# GearIndicator_pwr.net
KiCad netlist of a schematic drawn in EAGLE
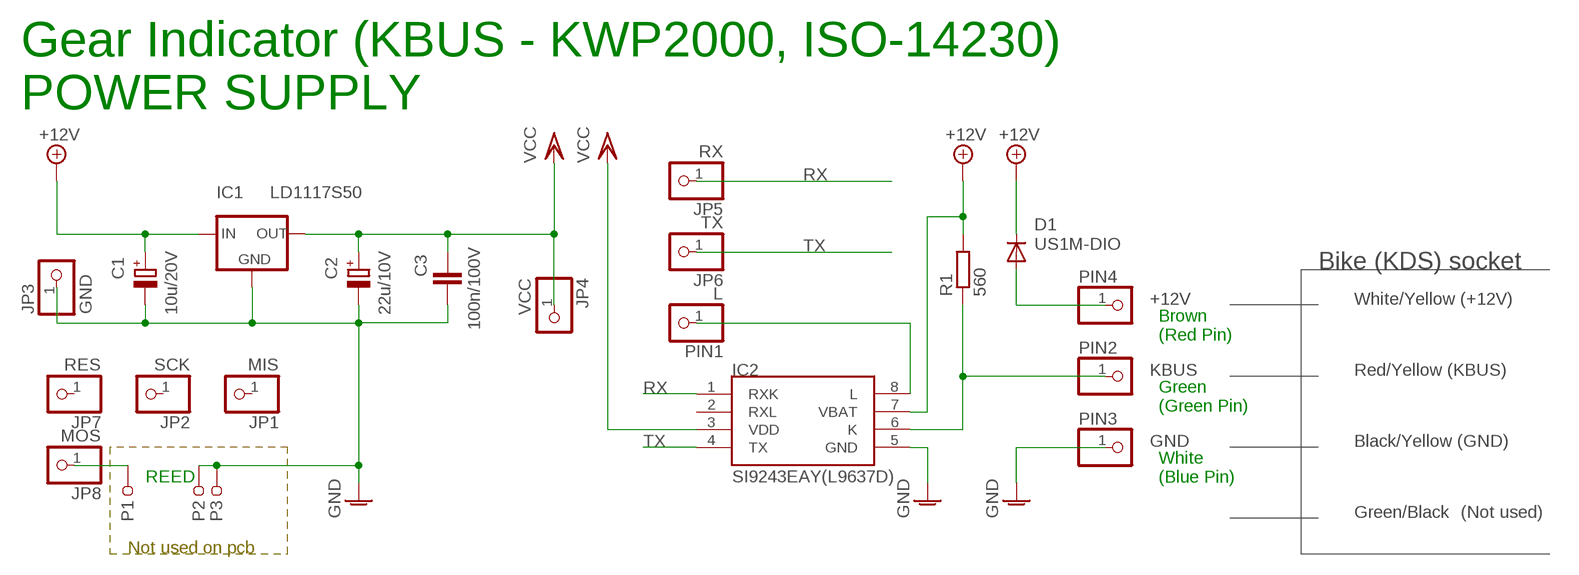
[diagram p0: schematic, sheet 1]

(export (version "E")
  (design (tool "Eeschema 10.0.6"))
  (components
    (comp (ref "C1")
      (value "10u/20V")
      (footprint "eagle-import:CT3216")
      (libsource (lib "eagle-import") (part "CPOL-EUCT3216"))
    )
    (comp (ref "C2")
      (value "22u/10V")
      (footprint "eagle-import:CT3216")
      (libsource (lib "eagle-import") (part "CPOL-EUCT3216"))
    )
    (comp (ref "C3")
      (value "100n/100V")
      (footprint "eagle-import:C1206")
      (libsource (lib "eagle-import") (part "C-EUC1206"))
    )
    (comp (ref "D1")
      (value "US1M-DIO")
      (footprint "eagle-import:DO-214AC")
      (libsource (lib "eagle-import") (part "DIODE-DO-214AC"))
    )
    (comp (ref "IC1")
      (value "LD1117S50")
      (footprint "eagle-import:SOT223")
      (libsource (lib "eagle-import") (part "AMS1117"))
    )
    (comp (ref "IC2")
      (value "SI9243EAY(L9637D)")
      (footprint "eagle-import:SO08")
      (libsource (lib "eagle-import") (part "SI9243"))
    )
    (comp (ref "JP1")
      (value "MIS")
      (footprint "eagle-import:1X01")
      (libsource (lib "eagle-import") (part "PINHD-1X1"))
    )
    (comp (ref "JP2")
      (value "SCK")
      (footprint "eagle-import:1X01")
      (libsource (lib "eagle-import") (part "PINHD-1X1"))
    )
    (comp (ref "JP3")
      (value "GND")
      (footprint "eagle-import:1X01")
      (libsource (lib "eagle-import") (part "PINHD-1X1"))
    )
    (comp (ref "JP4")
      (value "VCC")
      (footprint "eagle-import:1X01")
      (libsource (lib "eagle-import") (part "PINHD-1X1"))
    )
    (comp (ref "JP5")
      (value "RX")
      (footprint "eagle-import:1X01")
      (libsource (lib "eagle-import") (part "PINHD-1X1"))
    )
    (comp (ref "JP6")
      (value "TX")
      (footprint "eagle-import:1X01")
      (libsource (lib "eagle-import") (part "PINHD-1X1"))
    )
    (comp (ref "JP7")
      (value "RES")
      (footprint "eagle-import:1X01")
      (libsource (lib "eagle-import") (part "PINHD-1X1"))
    )
    (comp (ref "JP8")
      (value "MOS")
      (footprint "eagle-import:1X01")
      (libsource (lib "eagle-import") (part "PINHD-1X1"))
    )
    (comp (ref "P1")
      (value "SMD2")
      (footprint "eagle-import:SMD_2X1")
      (libsource (lib "eagle-import") (part "SMD2"))
    )
    (comp (ref "P2")
      (value "SMD2")
      (footprint "eagle-import:SMD_2X1")
      (libsource (lib "eagle-import") (part "SMD2"))
    )
    (comp (ref "P3")
      (value "SMD2")
      (footprint "eagle-import:SMD_2X1")
      (libsource (lib "eagle-import") (part "SMD2"))
    )
    (comp (ref "PIN1")
      (value "L")
      (footprint "eagle-import:PIN1")
      (libsource (lib "eagle-import") (part "PIN1"))
    )
    (comp (ref "PIN2")
      (value "KBUS")
      (footprint "eagle-import:PIN1")
      (libsource (lib "eagle-import") (part "PIN1"))
    )
    (comp (ref "PIN3")
      (value "GND")
      (footprint "eagle-import:PIN1")
      (libsource (lib "eagle-import") (part "PIN1"))
    )
    (comp (ref "PIN4")
      (value "+12V")
      (footprint "eagle-import:PIN1")
      (libsource (lib "eagle-import") (part "PIN1"))
    )
    (comp (ref "R1")
      (value "560")
      (footprint "eagle-import:R1206")
      (libsource (lib "eagle-import") (part "R-EU_R1206"))
    )
  )
  (nets
    (net (code "1") (name "+12V") (class "Default")
      (node (ref "C1") (pin "+") (pinfunction "+_+") (pintype "passive"))
      (node (ref "D1") (pin "C") (pinfunction "C_C") (pintype "passive"))
      (node (ref "IC1") (pin "3") (pinfunction "IN_3") (pintype "input"))
      (node (ref "IC2") (pin "7") (pinfunction "VBAT_7") (pintype "power_in"))
      (node (ref "R1") (pin "2") (pinfunction "2_2") (pintype "passive"))
    )
    (net (code "2") (name "/RX") (class "Default")
      (node (ref "IC2") (pin "1") (pinfunction "RXK_1") (pintype "bidirectional"))
      (node (ref "JP5") (pin "1") (pinfunction "1_1") (pintype "passive"))
    )
    (net (code "3") (name "/TX") (class "Default")
      (node (ref "IC2") (pin "4") (pinfunction "TX_4") (pintype "bidirectional"))
      (node (ref "JP6") (pin "1") (pinfunction "1_1") (pintype "passive"))
    )
    (net (code "4") (name "GND") (class "Default")
      (node (ref "C1") (pin "-") (pinfunction "-_-") (pintype "passive"))
      (node (ref "C2") (pin "-") (pinfunction "-_-") (pintype "passive"))
      (node (ref "C3") (pin "2") (pinfunction "2_2") (pintype "passive"))
      (node (ref "IC1") (pin "1") (pinfunction "GND_1") (pintype "input"))
      (node (ref "IC2") (pin "5") (pinfunction "GND_5") (pintype "power_in"))
      (node (ref "JP3") (pin "1") (pinfunction "1_1") (pintype "passive"))
      (node (ref "P2") (pin "P$1") (pinfunction "1_P$1") (pintype "passive"))
      (node (ref "P3") (pin "P$1") (pinfunction "1_P$1") (pintype "passive"))
      (node (ref "PIN3") (pin "1") (pinfunction "1_1") (pintype "passive"))
    )
    (net (code "5") (name "Net-(D1-PadA)") (class "Default")
      (node (ref "D1") (pin "A") (pinfunction "A_A") (pintype "passive"))
      (node (ref "PIN4") (pin "1") (pinfunction "1_1") (pintype "passive"))
    )
    (net (code "6") (name "Net-(IC2-K)") (class "Default")
      (node (ref "IC2") (pin "6") (pinfunction "K_6") (pintype "bidirectional"))
      (node (ref "PIN2") (pin "1") (pinfunction "1_1") (pintype "passive"))
      (node (ref "R1") (pin "1") (pinfunction "1_1") (pintype "passive"))
    )
    (net (code "7") (name "Net-(IC2-L)") (class "Default")
      (node (ref "IC2") (pin "8") (pinfunction "L_8") (pintype "bidirectional"))
      (node (ref "PIN1") (pin "1") (pinfunction "1_1") (pintype "passive"))
    )
    (net (code "8") (name "Net-(P1-1)") (class "Default")
      (node (ref "JP8") (pin "1") (pinfunction "1_1") (pintype "passive"))
      (node (ref "P1") (pin "P$1") (pinfunction "1_P$1") (pintype "passive"))
    )
    (net (code "9") (name "VCC") (class "Default")
      (node (ref "C2") (pin "+") (pinfunction "+_+") (pintype "passive"))
      (node (ref "C3") (pin "1") (pinfunction "1_1") (pintype "passive"))
      (node (ref "IC1") (pin "2") (pinfunction "OUT_2") (pintype "passive"))
      (node (ref "IC2") (pin "3") (pinfunction "VDD_3") (pintype "power_in"))
      (node (ref "JP4") (pin "1") (pinfunction "1_1") (pintype "passive"))
    )
    (net (code "10") (name "unconnected-(IC2-RXL-Pad2)") (class "Default")
      (node (ref "IC2") (pin "2") (pinfunction "RXL_2") (pintype "bidirectional"))
    )
    (net (code "11") (name "unconnected-(JP1-Pad1)") (class "Default")
      (node (ref "JP1") (pin "1") (pinfunction "1_1") (pintype "passive"))
    )
    (net (code "12") (name "unconnected-(JP2-Pad1)") (class "Default")
      (node (ref "JP2") (pin "1") (pinfunction "1_1") (pintype "passive"))
    )
    (net (code "13") (name "unconnected-(JP7-Pad1)") (class "Default")
      (node (ref "JP7") (pin "1") (pinfunction "1_1") (pintype "passive"))
    )
  )
)
